# Front_Node_MiniLock.net
KiCad netlist of a schematic drawn in EAGLE
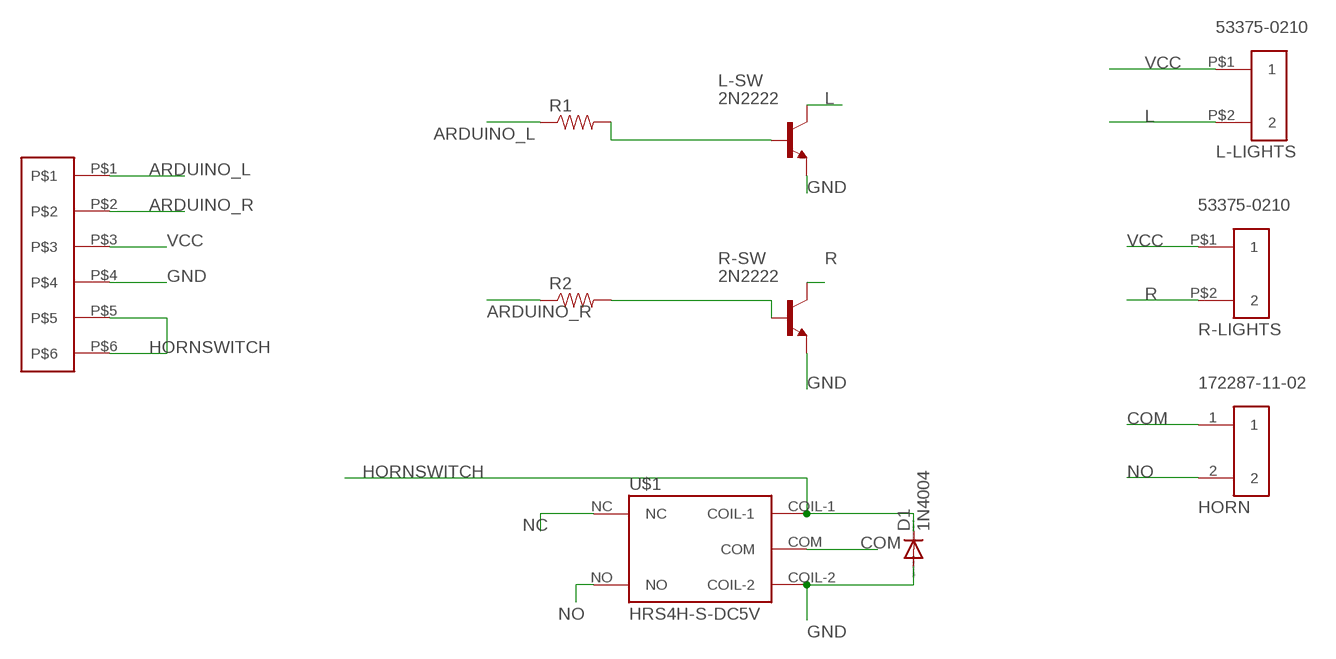
[diagram p0: schematic, sheet 1]

(export (version "E")
  (design (tool "Eeschema 10.0.6"))
  (components
    (comp (ref "ARDUINO")
      (value "53375-0610")
      (footprint "eagle-import:53375-0610-MINI-LOCK")
      (libsource (lib "eagle-import") (part "53375-0610"))
    )
    (comp (ref "D1")
      (value "1N4004")
      (footprint "eagle-import:DO41-10")
      (libsource (lib "eagle-import") (part "1N4004"))
    )
    (comp (ref "HORN")
      (value "172287-11-02")
      (footprint "eagle-import:172287-ULTRA-FIT")
      (libsource (lib "eagle-import") (part "172287-11-02"))
    )
    (comp (ref "L-LIGHTS")
      (value "53375-0210")
      (footprint "eagle-import:53375-0210-MINI-LOCK")
      (libsource (lib "eagle-import") (part "53375-0210"))
    )
    (comp (ref "L-SW")
      (value "2N2222")
      (footprint "eagle-import:TO18")
      (libsource (lib "eagle-import") (part "2N2222"))
    )
    (comp (ref "R-LIGHTS")
      (value "53375-0210")
      (footprint "eagle-import:53375-0210-MINI-LOCK")
      (libsource (lib "eagle-import") (part "53375-0210"))
    )
    (comp (ref "R-SW")
      (value "2N2222")
      (footprint "eagle-import:TO18")
      (libsource (lib "eagle-import") (part "2N2222"))
    )
    (comp (ref "R1")
      (value "RESISTORPTH-1/4W")
      (footprint "eagle-import:AXIAL-0.4")
      (libsource (lib "eagle-import") (part "RESISTORPTH-1/4W"))
    )
    (comp (ref "R2")
      (value "RESISTORPTH-1/4W")
      (footprint "eagle-import:AXIAL-0.4")
      (libsource (lib "eagle-import") (part "RESISTORPTH-1/4W"))
    )
    (comp (ref "U$1")
      (value "HRS4H-S-DC5V")
      (footprint "eagle-import:RELAY")
      (libsource (lib "eagle-import") (part "HRS4H-S-DC5V"))
    )
  )
  (nets
    (net (code "1") (name "/ARDUINO_L") (class "Default")
      (node (ref "ARDUINO") (pin "P$1") (pinfunction "P$1_P$1") (pintype "bidirectional"))
      (node (ref "R1") (pin "P$1") (pinfunction "1_P$1") (pintype "passive"))
    )
    (net (code "2") (name "/ARDUINO_R") (class "Default")
      (node (ref "ARDUINO") (pin "P$2") (pinfunction "P$2_P$2") (pintype "bidirectional"))
      (node (ref "R2") (pin "P$1") (pinfunction "1_P$1") (pintype "passive"))
    )
    (net (code "3") (name "/COM") (class "Default")
      (node (ref "HORN") (pin "1") (pinfunction "1_1") (pintype "bidirectional"))
      (node (ref "U$1") (pin "COM") (pinfunction "COM_COM") (pintype "bidirectional"))
    )
    (net (code "4") (name "/GND") (class "Default")
      (node (ref "ARDUINO") (pin "P$4") (pinfunction "P$4_P$4") (pintype "bidirectional"))
      (node (ref "D1") (pin "A") (pinfunction "A_A") (pintype "passive"))
      (node (ref "L-SW") (pin "1") (pinfunction "E_1") (pintype "passive"))
      (node (ref "R-SW") (pin "1") (pinfunction "E_1") (pintype "passive"))
      (node (ref "U$1") (pin "COIL-2") (pinfunction "COIL-2_COIL-2") (pintype "power_in"))
    )
    (net (code "5") (name "/HORNSWITCH") (class "Default")
      (node (ref "ARDUINO") (pin "P$5") (pinfunction "P$5_P$5") (pintype "bidirectional"))
      (node (ref "ARDUINO") (pin "P$6") (pinfunction "P$6_P$6") (pintype "bidirectional"))
      (node (ref "D1") (pin "C") (pinfunction "C_C") (pintype "passive"))
      (node (ref "U$1") (pin "COIL-1") (pinfunction "COIL-1_COIL-1") (pintype "power_in"))
    )
    (net (code "6") (name "/L") (class "Default")
      (node (ref "L-LIGHTS") (pin "P$2") (pinfunction "2_P$2") (pintype "bidirectional"))
      (node (ref "L-SW") (pin "3") (pinfunction "C_3") (pintype "passive"))
    )
    (net (code "7") (name "/NC") (class "Default")
      (node (ref "U$1") (pin "NC") (pinfunction "NC_NC") (pintype "bidirectional"))
    )
    (net (code "8") (name "/NO") (class "Default")
      (node (ref "HORN") (pin "2") (pinfunction "2_2") (pintype "bidirectional"))
      (node (ref "U$1") (pin "NO") (pinfunction "NO_NO") (pintype "bidirectional"))
    )
    (net (code "9") (name "/R") (class "Default")
      (node (ref "R-LIGHTS") (pin "P$2") (pinfunction "2_P$2") (pintype "bidirectional"))
      (node (ref "R-SW") (pin "3") (pinfunction "C_3") (pintype "passive"))
    )
    (net (code "10") (name "/VCC") (class "Default")
      (node (ref "ARDUINO") (pin "P$3") (pinfunction "P$3_P$3") (pintype "bidirectional"))
      (node (ref "L-LIGHTS") (pin "P$1") (pinfunction "1_P$1") (pintype "bidirectional"))
      (node (ref "R-LIGHTS") (pin "P$1") (pinfunction "1_P$1") (pintype "bidirectional"))
    )
    (net (code "11") (name "Net-(L-SW-B)") (class "Default")
      (node (ref "L-SW") (pin "2") (pinfunction "B_2") (pintype "passive"))
      (node (ref "R1") (pin "P$2") (pinfunction "2_P$2") (pintype "passive"))
    )
    (net (code "12") (name "Net-(R-SW-B)") (class "Default")
      (node (ref "R-SW") (pin "2") (pinfunction "B_2") (pintype "passive"))
      (node (ref "R2") (pin "P$2") (pinfunction "2_P$2") (pintype "passive"))
    )
  )
)
